# Arduino_4_Layer.net
KiCad netlist of a schematic drawn in Altium Designer
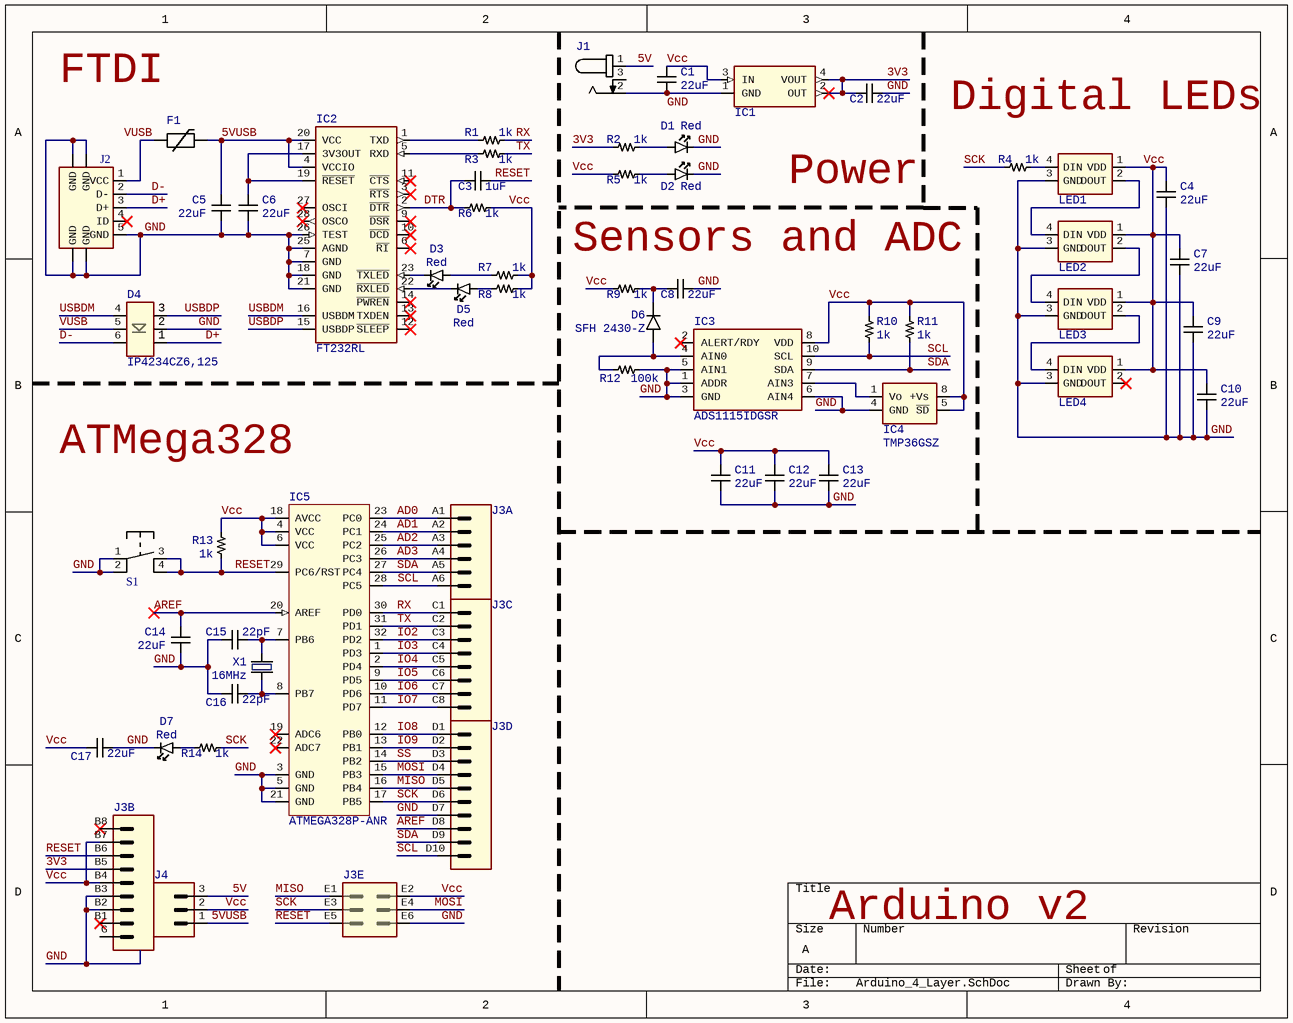
[diagram p0: Arduino_4_Layer.SchDoc]

(export (version "E")
  (design (tool "Eeschema 10.0.6"))
  (components
    (comp (ref "C1")
      (value "22uF")
      (footprint "CAP1206")
      (description "22µF ±20% 16V Ceramic Capacitor X5R 1206 (3216 Metric)")
      (fields (field (name "DIGIKEY PART") "1276-2728-1-ND"))
      (libsource (lib "Arduino_4_Layer") (part "1206_22uF"))
    )
    (comp (ref "C2")
      (value "22uF")
      (footprint "CAP1206")
      (description "22µF ±20% 16V Ceramic Capacitor X5R 1206 (3216 Metric)")
      (fields (field (name "DIGIKEY PART") "1276-2728-1-ND"))
      (libsource (lib "Arduino_4_Layer") (part "1206_22uF"))
    )
    (comp (ref "C3")
      (value "1uF")
      (footprint "CAP1206")
      (description "1µF ±20% 16V Ceramic Capacitor X7R 1206 (3216 Metric)")
      (fields (field (name "DIGIKEY PART") "399-8150-1-ND"))
      (libsource (lib "Arduino_4_Layer") (part "1206_1uF"))
    )
    (comp (ref "C4")
      (value "22uF")
      (footprint "CAP1206")
      (description "22µF ±20% 16V Ceramic Capacitor X5R 1206 (3216 Metric)")
      (fields (field (name "DIGIKEY PART") "1276-2728-1-ND"))
      (libsource (lib "Arduino_4_Layer") (part "1206_22uF"))
    )
    (comp (ref "C5")
      (value "22uF")
      (footprint "CAP1206")
      (description "22µF ±20% 16V Ceramic Capacitor X5R 1206 (3216 Metric)")
      (fields (field (name "DIGIKEY PART") "1276-2728-1-ND"))
      (libsource (lib "Arduino_4_Layer") (part "1206_22uF"))
    )
    (comp (ref "C6")
      (value "22uF")
      (footprint "CAP1206")
      (description "22µF ±20% 16V Ceramic Capacitor X5R 1206 (3216 Metric)")
      (fields (field (name "DIGIKEY PART") "1276-2728-1-ND"))
      (libsource (lib "Arduino_4_Layer") (part "1206_22uF"))
    )
    (comp (ref "C7")
      (value "22uF")
      (footprint "CAP1206")
      (description "22µF ±20% 16V Ceramic Capacitor X5R 1206 (3216 Metric)")
      (fields (field (name "DIGIKEY PART") "1276-2728-1-ND"))
      (libsource (lib "Arduino_4_Layer") (part "1206_22uF"))
    )
    (comp (ref "C8")
      (value "22uF")
      (footprint "CAP1206")
      (description "22µF ±20% 16V Ceramic Capacitor X5R 1206 (3216 Metric)")
      (fields (field (name "DIGIKEY PART") "1276-2728-1-ND"))
      (libsource (lib "Arduino_4_Layer") (part "1206_22uF"))
    )
    (comp (ref "C9")
      (value "22uF")
      (footprint "CAP1206")
      (description "22µF ±20% 16V Ceramic Capacitor X5R 1206 (3216 Metric)")
      (fields (field (name "DIGIKEY PART") "1276-2728-1-ND"))
      (libsource (lib "Arduino_4_Layer") (part "1206_22uF"))
    )
    (comp (ref "C10")
      (value "22uF")
      (footprint "CAP1206")
      (description "22µF ±20% 16V Ceramic Capacitor X5R 1206 (3216 Metric)")
      (fields (field (name "DIGIKEY PART") "1276-2728-1-ND"))
      (libsource (lib "Arduino_4_Layer") (part "1206_22uF"))
    )
    (comp (ref "C11")
      (value "22uF")
      (footprint "CAP1206")
      (description "22µF ±20% 16V Ceramic Capacitor X5R 1206 (3216 Metric)")
      (fields (field (name "DIGIKEY PART") "1276-2728-1-ND"))
      (libsource (lib "Arduino_4_Layer") (part "1206_22uF"))
    )
    (comp (ref "C12")
      (value "22uF")
      (footprint "CAP1206")
      (description "22µF ±20% 16V Ceramic Capacitor X5R 1206 (3216 Metric)")
      (fields (field (name "DIGIKEY PART") "1276-2728-1-ND"))
      (libsource (lib "Arduino_4_Layer") (part "1206_22uF"))
    )
    (comp (ref "C13")
      (value "22uF")
      (footprint "CAP1206")
      (description "22µF ±20% 16V Ceramic Capacitor X5R 1206 (3216 Metric)")
      (fields (field (name "DIGIKEY PART") "1276-2728-1-ND"))
      (libsource (lib "Arduino_4_Layer") (part "1206_22uF"))
    )
    (comp (ref "C14")
      (value "22uF")
      (footprint "CAP1206")
      (description "22µF ±20% 16V Ceramic Capacitor X5R 1206 (3216 Metric)")
      (fields (field (name "DIGIKEY PART") "1276-2728-1-ND"))
      (libsource (lib "Arduino_4_Layer") (part "1206_22uF"))
    )
    (comp (ref "C15")
      (value "22pF")
      (footprint "CAP1206")
      (description "22pF ±5% 16V Ceramic Capacitor C0G, NP0 1206 (3216 Metric)")
      (fields (field (name "DIGIKEY PART") "732-7867-1-ND"))
      (libsource (lib "Arduino_4_Layer") (part "1206_22pF"))
    )
    (comp (ref "C16")
      (value "22pF")
      (footprint "CAP1206")
      (description "22pF ±5% 16V Ceramic Capacitor C0G, NP0 1206 (3216 Metric)")
      (fields (field (name "DIGIKEY PART") "732-7867-1-ND"))
      (libsource (lib "Arduino_4_Layer") (part "1206_22pF"))
    )
    (comp (ref "C17")
      (value "22uF")
      (footprint "CAP1206")
      (description "22µF ±20% 16V Ceramic Capacitor X5R 1206 (3216 Metric)")
      (fields (field (name "DIGIKEY PART") "1276-2728-1-ND"))
      (libsource (lib "Arduino_4_Layer") (part "1206_22uF"))
    )
    (comp (ref "D1")
      (value "Red")
      (footprint "LED")
      (description "Red 638nm LED Indication - Discrete 1.8V 1206 (3216 Metric)")
      (fields (field (name "DIGIKEY PART") "160-1167-1-ND"))
      (libsource (lib "Arduino_4_Layer") (part "1206_RED_LED"))
    )
    (comp (ref "D2")
      (value "Red")
      (footprint "LED")
      (description "Red 638nm LED Indication - Discrete 1.8V 1206 (3216 Metric)")
      (fields (field (name "DIGIKEY PART") "160-1167-1-ND"))
      (libsource (lib "Arduino_4_Layer") (part "1206_RED_LED"))
    )
    (comp (ref "D3")
      (value "Red")
      (footprint "LED")
      (description "Red 638nm LED Indication - Discrete 1.8V 1206 (3216 Metric)")
      (fields (field (name "DIGIKEY PART") "160-1167-1-ND"))
      (libsource (lib "Arduino_4_Layer") (part "1206_RED_LED"))
    )
    (comp (ref "D4")
      (value "IP4234CZ6,125")
      (footprint "TSOP-6")
      (description "Clamp Ipp Tvs Diode Surface Mount 6-TSOP")
      (fields (field (name "DIGIKEY PART") "1727-4717-1-ND"))
      (libsource (lib "Arduino_4_Layer") (part "TVS_Diode"))
    )
    (comp (ref "D5")
      (value "Red")
      (footprint "LED")
      (description "Red 638nm LED Indication - Discrete 1.8V 1206 (3216 Metric)")
      (fields (field (name "DIGIKEY PART") "160-1167-1-ND"))
      (libsource (lib "Arduino_4_Layer") (part "1206_RED_LED"))
    )
    (comp (ref "D6")
      (value "SFH 2430-Z")
      (footprint "SFH 2430")
      (description "Ambient Light Sensor Photodiode Chip 570nm 0.17A/W Sensitivity Automotive 2-Pin DIL SMT")
      (fields (field (name "MANUFACTURER") "Osram Opto"))
      (libsource (lib "Arduino_4_Layer") (part "SFH 2430-Z"))
    )
    (comp (ref "D7")
      (value "Red")
      (footprint "LED")
      (description "Red 638nm LED Indication - Discrete 1.8V 1206 (3216 Metric)")
      (fields (field (name "DIGIKEY PART") "160-1167-1-ND"))
      (libsource (lib "Arduino_4_Layer") (part "1206_RED_LED"))
    )
    (comp (ref "F1")
      (value "MF-MSMF050-2")
      (footprint "FUSE")
      (description "Polymeric PTC Resettable Fuse 15V 500mA Ih Surface Mount 1812 (4532 Metric), Concave")
      (fields (field (name "DIGIKEY PART") "MF-MSMF050-2CT-ND"))
      (libsource (lib "Arduino_4_Layer") (part "Fuse"))
    )
    (comp (ref "IC1")
      (value "AZ1117CH-3.3TRG1")
      (footprint "SOT223")
      (description "Linear Voltage Regulator IC Positive Fixed 1 Output 1A SOT-223")
      (fields (field (name "DIGIKEY PART") "AZ1117CH-3.3TRG1DICT-ND"))
      (libsource (lib "Arduino_4_Layer") (part "3.3V_LDO"))
    )
    (comp (ref "IC2")
      (value "FT232RL")
      (footprint "SOP65P780X200-28N")
      (description "USB Bridge, USB to UART USB 2.0 UART Interface 28-SSOP")
      (fields (field (name "DIGIKEY PART") "768-1007-1-ND"))
      (libsource (lib "Arduino_4_Layer") (part "FTDI"))
    )
    (comp (ref "IC3")
      (value "ADS1115IDGSR")
      (footprint "VSSOP-10")
      (description "4-Channel Single ADC Delta-Sigma 860sps 16-bit Serial 10-Pin VSSOP T/R")
      (fields (field (name "MANUFACTURER") "Texas Instruments"))
      (libsource (lib "Arduino_4_Layer") (part "ADS1115IDGSR"))
    )
    (comp (ref "IC4")
      (value "TMP36GSZ")
      (footprint "SOIC-8")
      (description "Temp Sensor Analog(Voltage) Serial (2-Wire) 8-Pin SOIC N Tube")
      (fields (field (name "MANUFACTURER") "Analog Devices"))
      (libsource (lib "Arduino_4_Layer") (part "TMP36GSZ"))
    )
    (comp (ref "IC5")
      (value "ATMEGA328P-ANR")
      (footprint "TQFP-32")
      (description "AVR AVR® ATmega Microcontroller IC 8-Bit 20MHz 32KB (16K x 16) FLASH 32-TQFP (7x7)")
      (fields (field (name "DIGIKEY PART") "ATMEGA328P-ANRCT-ND"))
      (libsource (lib "Arduino_4_Layer") (part "ATMega328P"))
    )
    (comp (ref "J1")
      (value "Power Jack")
      (footprint "Power_Jack")
      (description "Power Barrel Connector Jack 2.10mm ID (0.083\"), 5.50mm OD (0.217\") Through Hole, Right Angle")
      (fields (field (name "DIGIKEY PART") "CP-102A-ND"))
      (libsource (lib "Arduino_4_Layer") (part "Power Jack"))
    )
    (comp (ref "J2")
      (value "XM7D-0512")
      (footprint "XM7D-0512")
      (description "USB - mini B USB 2.0 Receptacle Connector 5 Position Through Hole, Right Angle")
      (fields (field (name "DIGIKEY PART") "OR1205-ND"))
      (libsource (lib "Arduino_4_Layer") (part "USB"))
    )
    (comp (ref "J3")
      (value "Arduino_Shield")
      (footprint "ARDUINO_SHIELD")
      (libsource (lib "Arduino_4_Layer") (part "Arduino_Shield"))
    )
    (comp (ref "J4")
      (value "PREC003SAAN-RC")
      (footprint "3_PIN")
      (description "Connector Header Through Hole 3 position 0.100\" (2.54mm)")
      (fields (field (name "DIGIKEY PART") "S1012EC-03-ND"))
      (libsource (lib "Arduino_4_Layer") (part "3_PIN"))
    )
    (comp (ref "LED1")
      (value "IN-PI55QATPRPGPBPW-60")
      (footprint "PLCC_5x5")
      (description "Top View Plcc 5.0X5.0X1.6 4-PIN")
      (fields (field (name "MANUFACTURER") "Inolux"))
      (libsource (lib "Arduino_4_Layer") (part "IN-PI55QATPRPGPBPW-60"))
    )
    (comp (ref "LED2")
      (value "IN-PI55QATPRPGPBPW-60")
      (footprint "PLCC_5x5")
      (description "Top View Plcc 5.0X5.0X1.6 4-PIN")
      (fields (field (name "MANUFACTURER") "Inolux"))
      (libsource (lib "Arduino_4_Layer") (part "IN-PI55QATPRPGPBPW-60"))
    )
    (comp (ref "LED3")
      (value "IN-PI55QATPRPGPBPW-60")
      (footprint "PLCC_5x5")
      (description "Top View Plcc 5.0X5.0X1.6 4-PIN")
      (fields (field (name "MANUFACTURER") "Inolux"))
      (libsource (lib "Arduino_4_Layer") (part "IN-PI55QATPRPGPBPW-60"))
    )
    (comp (ref "LED4")
      (value "IN-PI55QATPRPGPBPW-60")
      (footprint "PLCC_5x5")
      (description "Top View Plcc 5.0X5.0X1.6 4-PIN")
      (fields (field (name "MANUFACTURER") "Inolux"))
      (libsource (lib "Arduino_4_Layer") (part "IN-PI55QATPRPGPBPW-60"))
    )
    (comp (ref "R1")
      (value "1k")
      (footprint "RES1206")
      (description "1 kOhms ±1% 0.5W, 1/2W Chip Resistor 1206 (3216 Metric) Anti-Sulfur, Moisture Resistant Thin Film")
      (fields (field (name "DIGIKEY PART") "RNCP1206FTD1K00CT-ND"))
      (libsource (lib "Arduino_4_Layer") (part "1206_1K"))
    )
    (comp (ref "R2")
      (value "1k")
      (footprint "RES1206")
      (description "1 kOhms ±1% 0.5W, 1/2W Chip Resistor 1206 (3216 Metric) Anti-Sulfur, Moisture Resistant Thin Film")
      (fields (field (name "DIGIKEY PART") "RNCP1206FTD1K00CT-ND"))
      (libsource (lib "Arduino_4_Layer") (part "1206_1K"))
    )
    (comp (ref "R3")
      (value "1k")
      (footprint "RES1206")
      (description "1 kOhms ±1% 0.5W, 1/2W Chip Resistor 1206 (3216 Metric) Anti-Sulfur, Moisture Resistant Thin Film")
      (fields (field (name "DIGIKEY PART") "RNCP1206FTD1K00CT-ND"))
      (libsource (lib "Arduino_4_Layer") (part "1206_1K"))
    )
    (comp (ref "R4")
      (value "1k")
      (footprint "RES1206")
      (description "1 kOhms ±1% 0.5W, 1/2W Chip Resistor 1206 (3216 Metric) Anti-Sulfur, Moisture Resistant Thin Film")
      (fields (field (name "DIGIKEY PART") "RNCP1206FTD1K00CT-ND"))
      (libsource (lib "Arduino_4_Layer") (part "1206_1K"))
    )
    (comp (ref "R5")
      (value "1k")
      (footprint "RES1206")
      (description "1 kOhms ±1% 0.5W, 1/2W Chip Resistor 1206 (3216 Metric) Anti-Sulfur, Moisture Resistant Thin Film")
      (fields (field (name "DIGIKEY PART") "RNCP1206FTD1K00CT-ND"))
      (libsource (lib "Arduino_4_Layer") (part "1206_1K"))
    )
    (comp (ref "R6")
      (value "1k")
      (footprint "RES1206")
      (description "1 kOhms ±1% 0.5W, 1/2W Chip Resistor 1206 (3216 Metric) Anti-Sulfur, Moisture Resistant Thin Film")
      (fields (field (name "DIGIKEY PART") "RNCP1206FTD1K00CT-ND"))
      (libsource (lib "Arduino_4_Layer") (part "1206_1K"))
    )
    (comp (ref "R7")
      (value "1k")
      (footprint "RES1206")
      (description "1 kOhms ±1% 0.5W, 1/2W Chip Resistor 1206 (3216 Metric) Anti-Sulfur, Moisture Resistant Thin Film")
      (fields (field (name "DIGIKEY PART") "RNCP1206FTD1K00CT-ND"))
      (libsource (lib "Arduino_4_Layer") (part "1206_1K"))
    )
    (comp (ref "R8")
      (value "1k")
      (footprint "RES1206")
      (description "1 kOhms ±1% 0.5W, 1/2W Chip Resistor 1206 (3216 Metric) Anti-Sulfur, Moisture Resistant Thin Film")
      (fields (field (name "DIGIKEY PART") "RNCP1206FTD1K00CT-ND"))
      (libsource (lib "Arduino_4_Layer") (part "1206_1K"))
    )
    (comp (ref "R9")
      (value "1k")
      (footprint "RES1206")
      (description "1 kOhms ±1% 0.5W, 1/2W Chip Resistor 1206 (3216 Metric) Anti-Sulfur, Moisture Resistant Thin Film")
      (fields (field (name "DIGIKEY PART") "RNCP1206FTD1K00CT-ND"))
      (libsource (lib "Arduino_4_Layer") (part "1206_1K"))
    )
    (comp (ref "R10")
      (value "1k")
      (footprint "RES1206")
      (description "1 kOhms ±1% 0.5W, 1/2W Chip Resistor 1206 (3216 Metric) Anti-Sulfur, Moisture Resistant Thin Film")
      (fields (field (name "DIGIKEY PART") "RNCP1206FTD1K00CT-ND"))
      (libsource (lib "Arduino_4_Layer") (part "1206_1K"))
    )
    (comp (ref "R11")
      (value "1k")
      (footprint "RES1206")
      (description "1 kOhms ±1% 0.5W, 1/2W Chip Resistor 1206 (3216 Metric) Anti-Sulfur, Moisture Resistant Thin Film")
      (fields (field (name "DIGIKEY PART") "RNCP1206FTD1K00CT-ND"))
      (libsource (lib "Arduino_4_Layer") (part "1206_1K"))
    )
    (comp (ref "R12")
      (value "100k")
      (footprint "RES1206")
      (description "100 kOhms ±5% 0.25W, 1/4W Chip Resistor 1206 (3216 Metric) Automotive AEC-Q200 Thick Film")
      (libsource (lib "Arduino_4_Layer") (part "1206_100k"))
    )
    (comp (ref "R13")
      (value "1k")
      (footprint "RES1206")
      (description "1 kOhms ±1% 0.5W, 1/2W Chip Resistor 1206 (3216 Metric) Anti-Sulfur, Moisture Resistant Thin Film")
      (fields (field (name "DIGIKEY PART") "RNCP1206FTD1K00CT-ND"))
      (libsource (lib "Arduino_4_Layer") (part "1206_1K"))
    )
    (comp (ref "R14")
      (value "1k")
      (footprint "RES1206")
      (description "1 kOhms ±1% 0.5W, 1/2W Chip Resistor 1206 (3216 Metric) Anti-Sulfur, Moisture Resistant Thin Film")
      (fields (field (name "DIGIKEY PART") "RNCP1206FTD1K00CT-ND"))
      (libsource (lib "Arduino_4_Layer") (part "1206_1K"))
    )
    (comp (ref "S1")
      (value "TL3305AF160QG")
      (footprint "Switch")
      (description "Tactile Switch SPST-NO Top Actuated Surface Mount")
      (fields (field (name "DIGIKEY PART") "EG5350CT-ND"))
      (libsource (lib "Arduino_4_Layer") (part "Push_Button"))
    )
    (comp (ref "X1")
      (value "16MHz")
      (footprint "Crystal")
      (description "16MHz ±30ppm Crystal 18pF 40 Ohms HC-49/US")
      (fields (field (name "DIGIKEY PART") "535-10226-1-ND"))
      (libsource (lib "Arduino_4_Layer") (part "16MHz_Crystal"))
    )
  )
  (nets
    (net (code "1") (name "/3V3") (class "Default")
      (node (ref "C2") (pin "2") (pinfunction "2_2") (pintype "passive"))
      (node (ref "IC1") (pin "2") (pinfunction "OUT_2") (pintype "output"))
      (node (ref "IC1") (pin "4") (pinfunction "VOUT_4") (pintype "output"))
      (node (ref "J3") (pin "B5") (pinfunction "5_B5") (pintype "passive"))
      (node (ref "R2") (pin "2") (pintype "passive"))
    )
    (net (code "2") (name "/5V") (class "Default")
      (node (ref "J1") (pin "1") (pinfunction "1_1") (pintype "passive"))
      (node (ref "J4") (pin "3") (pinfunction "3_3") (pintype "passive"))
    )
    (net (code "3") (name "/5VUSB") (class "Default")
      (node (ref "C5") (pin "2") (pinfunction "2_2") (pintype "passive"))
      (node (ref "F1") (pin "2") (pinfunction "2_2") (pintype "passive"))
      (node (ref "IC2") (pin "20") (pinfunction "VCC_20") (pintype "power_in"))
      (node (ref "IC2") (pin "4") (pinfunction "VCCIO_4") (pintype "power_in"))
      (node (ref "J4") (pin "1") (pinfunction "1_1") (pintype "passive"))
    )
    (net (code "4") (name "/AD0") (class "Default")
      (node (ref "IC5") (pin "23") (pinfunction "PC0_23") (pintype "bidirectional"))
      (node (ref "J3") (pin "A1") (pinfunction "1_A1") (pintype "passive"))
    )
    (net (code "5") (name "/AD1") (class "Default")
      (node (ref "IC5") (pin "24") (pinfunction "PC1_24") (pintype "bidirectional"))
      (node (ref "J3") (pin "A2") (pinfunction "2_A2") (pintype "passive"))
    )
    (net (code "6") (name "/AD2") (class "Default")
      (node (ref "IC5") (pin "25") (pinfunction "PC2_25") (pintype "bidirectional"))
      (node (ref "J3") (pin "A3") (pinfunction "3_A3") (pintype "passive"))
    )
    (net (code "7") (name "/AD3") (class "Default")
      (node (ref "IC5") (pin "26") (pinfunction "PC3_26") (pintype "bidirectional"))
      (node (ref "J3") (pin "A4") (pinfunction "4_A4") (pintype "passive"))
    )
    (net (code "8") (name "/AREF") (class "Default")
      (node (ref "C14") (pin "2") (pinfunction "2_2") (pintype "passive"))
      (node (ref "IC5") (pin "20") (pinfunction "AREF_20") (pintype "input"))
      (node (ref "J3") (pin "D8") (pinfunction "8_D8") (pintype "passive"))
    )
    (net (code "9") (name "/D+") (class "Default")
      (node (ref "D4") (pin "1") (pinfunction "1_1") (pintype "passive"))
      (node (ref "J2") (pin "3") (pinfunction "D+_3") (pintype "passive"))
    )
    (net (code "10") (name "/D-") (class "Default")
      (node (ref "D4") (pin "6") (pinfunction "6_6") (pintype "passive"))
      (node (ref "J2") (pin "2") (pinfunction "D-_2") (pintype "passive"))
    )
    (net (code "11") (name "/DTR") (class "Default")
      (node (ref "C3") (pin "1") (pinfunction "1_1") (pintype "passive"))
      (node (ref "IC2") (pin "2") (pinfunction "~{DTR}_2") (pintype "output"))
      (node (ref "R6") (pin "1") (pintype "passive"))
    )
    (net (code "12") (name "/GND") (class "Default")
      (node (ref "C1") (pin "2") (pinfunction "2_2") (pintype "passive"))
      (node (ref "C10") (pin "1") (pinfunction "1_1") (pintype "passive"))
      (node (ref "C11") (pin "1") (pinfunction "1_1") (pintype "passive"))
      (node (ref "C12") (pin "1") (pinfunction "1_1") (pintype "passive"))
      (node (ref "C13") (pin "1") (pinfunction "1_1") (pintype "passive"))
      (node (ref "C14") (pin "1") (pinfunction "1_1") (pintype "passive"))
      (node (ref "C15") (pin "1") (pinfunction "1_1") (pintype "passive"))
      (node (ref "C16") (pin "1") (pinfunction "1_1") (pintype "passive"))
      (node (ref "C17") (pin "1") (pinfunction "1_1") (pintype "passive"))
      (node (ref "C2") (pin "1") (pinfunction "1_1") (pintype "passive"))
      (node (ref "C4") (pin "1") (pinfunction "1_1") (pintype "passive"))
      (node (ref "C5") (pin "1") (pinfunction "1_1") (pintype "passive"))
      (node (ref "C6") (pin "1") (pinfunction "1_1") (pintype "passive"))
      (node (ref "C7") (pin "1") (pinfunction "1_1") (pintype "passive"))
      (node (ref "C8") (pin "2") (pinfunction "2_2") (pintype "passive"))
      (node (ref "C9") (pin "1") (pinfunction "1_1") (pintype "passive"))
      (node (ref "D1") (pin "1") (pinfunction "1_1") (pintype "passive"))
      (node (ref "D2") (pin "1") (pinfunction "1_1") (pintype "passive"))
      (node (ref "D4") (pin "2") (pinfunction "2_2") (pintype "passive"))
      (node (ref "D7") (pin "1") (pinfunction "1_1") (pintype "passive"))
      (node (ref "IC1") (pin "1") (pinfunction "GND_1") (pintype "passive"))
      (node (ref "IC2") (pin "18") (pinfunction "GND_18") (pintype "power_in"))
      (node (ref "IC2") (pin "21") (pinfunction "GND_21") (pintype "power_in"))
      (node (ref "IC2") (pin "25") (pinfunction "AGND_25") (pintype "power_in"))
      (node (ref "IC2") (pin "26") (pinfunction "TEST_26") (pintype "input"))
      (node (ref "IC2") (pin "7") (pinfunction "GND_7") (pintype "power_in"))
      (node (ref "IC3") (pin "1") (pinfunction "ADDR_1") (pintype "passive"))
      (node (ref "IC3") (pin "3") (pinfunction "GND_3") (pintype "passive"))
      (node (ref "IC3") (pin "5") (pinfunction "AIN1_5") (pintype "passive"))
      (node (ref "IC3") (pin "6") (pinfunction "AIN4_6") (pintype "passive"))
      (node (ref "IC4") (pin "4") (pinfunction "GND_4") (pintype "passive"))
      (node (ref "IC5") (pin "21") (pinfunction "GND_21") (pintype "power_in"))
      (node (ref "IC5") (pin "3") (pinfunction "GND_3") (pintype "power_in"))
      (node (ref "IC5") (pin "5") (pinfunction "GND_5") (pintype "power_in"))
      (node (ref "J1") (pin "2") (pinfunction "2_2") (pintype "passive"))
      (node (ref "J2") (pin "5") (pinfunction "GND_5") (pintype "passive"))
      (node (ref "J2") (pin "SH1") (pinfunction "GND_SH1") (pintype "passive"))
      (node (ref "J2") (pin "SH2") (pinfunction "GND_SH2") (pintype "passive"))
      (node (ref "J2") (pin "SH3") (pinfunction "GND_SH3") (pintype "passive"))
      (node (ref "J2") (pin "SH4") (pinfunction "GND_SH4") (pintype "passive"))
      (node (ref "J3") (pin "B2") (pinfunction "2_B2") (pintype "passive"))
      (node (ref "J3") (pin "B3") (pinfunction "3_B3") (pintype "passive"))
      (node (ref "J3") (pin "D7") (pinfunction "7_D7") (pintype "passive"))
      (node (ref "J3") (pin "E6") (pinfunction "6_E6") (pintype "passive"))
      (node (ref "LED1") (pin "3") (pinfunction "GND_3") (pintype "passive"))
      (node (ref "LED2") (pin "3") (pinfunction "GND_3") (pintype "passive"))
      (node (ref "LED3") (pin "3") (pinfunction "GND_3") (pintype "passive"))
      (node (ref "LED4") (pin "3") (pinfunction "GND_3") (pintype "passive"))
      (node (ref "R12") (pin "1") (pintype "passive"))
      (node (ref "S1") (pin "1") (pinfunction "1_1") (pintype "passive"))
      (node (ref "S1") (pin "2") (pinfunction "2_2") (pintype "passive"))
    )
    (net (code "13") (name "/IO2") (class "Default")
      (node (ref "IC5") (pin "32") (pinfunction "PD2_32") (pintype "bidirectional"))
      (node (ref "J3") (pin "C3") (pinfunction "3_C3") (pintype "passive"))
    )
    (net (code "14") (name "/IO3") (class "Default")
      (node (ref "IC5") (pin "1") (pinfunction "PD3_1") (pintype "bidirectional"))
      (node (ref "J3") (pin "C4") (pinfunction "4_C4") (pintype "passive"))
    )
    (net (code "15") (name "/IO4") (class "Default")
      (node (ref "IC5") (pin "2") (pinfunction "PD4_2") (pintype "bidirectional"))
      (node (ref "J3") (pin "C5") (pinfunction "5_C5") (pintype "passive"))
    )
    (net (code "16") (name "/IO5") (class "Default")
      (node (ref "IC5") (pin "9") (pinfunction "PD5_9") (pintype "bidirectional"))
      (node (ref "J3") (pin "C6") (pinfunction "6_C6") (pintype "passive"))
    )
    (net (code "17") (name "/IO6") (class "Default")
      (node (ref "IC5") (pin "10") (pinfunction "PD6_10") (pintype "bidirectional"))
      (node (ref "J3") (pin "C7") (pinfunction "7_C7") (pintype "passive"))
    )
    (net (code "18") (name "/IO7") (class "Default")
      (node (ref "IC5") (pin "11") (pinfunction "PD7_11") (pintype "bidirectional"))
      (node (ref "J3") (pin "C8") (pinfunction "8_C8") (pintype "passive"))
    )
    (net (code "19") (name "/IO8") (class "Default")
      (node (ref "IC5") (pin "12") (pinfunction "PB0_12") (pintype "bidirectional"))
      (node (ref "J3") (pin "D1") (pinfunction "1_D1") (pintype "passive"))
    )
    (net (code "20") (name "/IO9") (class "Default")
      (node (ref "IC5") (pin "13") (pinfunction "PB1_13") (pintype "bidirectional"))
      (node (ref "J3") (pin "D2") (pinfunction "2_D2") (pintype "passive"))
    )
    (net (code "21") (name "/MISO") (class "Default")
      (node (ref "IC5") (pin "16") (pinfunction "PB4_16") (pintype "bidirectional"))
      (node (ref "J3") (pin "D5") (pinfunction "5_D5") (pintype "passive"))
      (node (ref "J3") (pin "E1") (pinfunction "1_E1") (pintype "passive"))
    )
    (net (code "22") (name "/MOSI") (class "Default")
      (node (ref "IC5") (pin "15") (pinfunction "PB3_15") (pintype "bidirectional"))
      (node (ref "J3") (pin "D4") (pinfunction "4_D4") (pintype "passive"))
      (node (ref "J3") (pin "E4") (pinfunction "5_E4") (pintype "passive"))
    )
    (net (code "23") (name "/RESET") (class "Default")
      (node (ref "C3") (pin "2") (pinfunction "2_2") (pintype "passive"))
      (node (ref "IC5") (pin "29") (pinfunction "PC6/RST_29") (pintype "bidirectional"))
      (node (ref "J3") (pin "B6") (pinfunction "6_B6") (pintype "passive"))
      (node (ref "J3") (pin "E5") (pinfunction "3_E5") (pintype "passive"))
      (node (ref "R13") (pin "1") (pintype "passive"))
      (node (ref "S1") (pin "3") (pinfunction "3_3") (pintype "passive"))
      (node (ref "S1") (pin "4") (pinfunction "4_4") (pintype "passive"))
    )
    (net (code "24") (name "/RX") (class "Default")
      (node (ref "IC5") (pin "30") (pinfunction "PD0_30") (pintype "bidirectional"))
      (node (ref "J3") (pin "C1") (pinfunction "1_C1") (pintype "passive"))
      (node (ref "R1") (pin "2") (pintype "passive"))
    )
    (net (code "25") (name "/SCK") (class "Default")
      (node (ref "IC5") (pin "17") (pinfunction "PB5_17") (pintype "bidirectional"))
      (node (ref "J3") (pin "D6") (pinfunction "6_D6") (pintype "passive"))
      (node (ref "J3") (pin "E3") (pinfunction "2_E3") (pintype "passive"))
      (node (ref "R14") (pin "2") (pintype "passive"))
      (node (ref "R4") (pin "1") (pintype "passive"))
    )
    (net (code "26") (name "/SCL") (class "Default")
      (node (ref "IC3") (pin "10") (pinfunction "SCL_10") (pintype "passive"))
      (node (ref "IC5") (pin "28") (pinfunction "PC5_28") (pintype "bidirectional"))
      (node (ref "J3") (pin "A6") (pinfunction "6_A6") (pintype "passive"))
      (node (ref "J3") (pin "D10") (pinfunction "10_D10") (pintype "passive"))
      (node (ref "R10") (pin "1") (pintype "passive"))
    )
    (net (code "27") (name "/SDA") (class "Default")
      (node (ref "IC3") (pin "9") (pinfunction "SDA_9") (pintype "passive"))
      (node (ref "IC5") (pin "27") (pinfunction "PC4_27") (pintype "bidirectional"))
      (node (ref "J3") (pin "A5") (pinfunction "5_A5") (pintype "passive"))
      (node (ref "J3") (pin "D9") (pinfunction "9_D9") (pintype "passive"))
      (node (ref "R11") (pin "1") (pintype "passive"))
    )
    (net (code "28") (name "/SS") (class "Default")
      (node (ref "IC5") (pin "14") (pinfunction "PB2_14") (pintype "bidirectional"))
      (node (ref "J3") (pin "D3") (pinfunction "3_D3") (pintype "passive"))
    )
    (net (code "29") (name "/TX") (class "Default")
      (node (ref "IC5") (pin "31") (pinfunction "PD1_31") (pintype "bidirectional"))
      (node (ref "J3") (pin "C2") (pinfunction "2_C2") (pintype "passive"))
      (node (ref "R3") (pin "2") (pintype "passive"))
    )
    (net (code "30") (name "/USBDM") (class "Default")
      (node (ref "D4") (pin "4") (pinfunction "4_4") (pintype "passive"))
      (node (ref "IC2") (pin "16") (pinfunction "USBDM_16") (pintype "bidirectional"))
    )
    (net (code "31") (name "/USBDP") (class "Default")
      (node (ref "D4") (pin "3") (pinfunction "3_3") (pintype "passive"))
      (node (ref "IC2") (pin "15") (pinfunction "USBDP_15") (pintype "bidirectional"))
    )
    (net (code "32") (name "/VUSB") (class "Default")
      (node (ref "D4") (pin "5") (pinfunction "5_5") (pintype "passive"))
      (node (ref "F1") (pin "1") (pinfunction "1_1") (pintype "passive"))
      (node (ref "J2") (pin "1") (pinfunction "VCC_1") (pintype "passive"))
    )
    (net (code "33") (name "/Vcc") (class "Default")
      (node (ref "C1") (pin "1") (pinfunction "1_1") (pintype "passive"))
      (node (ref "C10") (pin "2") (pinfunction "2_2") (pintype "passive"))
      (node (ref "C11") (pin "2") (pinfunction "2_2") (pintype "passive"))
      (node (ref "C12") (pin "2") (pinfunction "2_2") (pintype "passive"))
      (node (ref "C13") (pin "2") (pinfunction "2_2") (pintype "passive"))
      (node (ref "C17") (pin "2") (pinfunction "2_2") (pintype "passive"))
      (node (ref "C4") (pin "2") (pinfunction "2_2") (pintype "passive"))
      (node (ref "C7") (pin "2") (pinfunction "2_2") (pintype "passive"))
      (node (ref "C9") (pin "2") (pinfunction "2_2") (pintype "passive"))
      (node (ref "IC1") (pin "3") (pinfunction "IN_3") (pintype "input"))
      (node (ref "IC3") (pin "8") (pinfunction "VDD_8") (pintype "passive"))
      (node (ref "IC4") (pin "5") (pinfunction "~{SD}_5") (pintype "passive"))
      (node (ref "IC4") (pin "8") (pinfunction "+Vs_8") (pintype "passive"))
      (node (ref "IC5") (pin "18") (pinfunction "AVCC_18") (pintype "power_in"))
      (node (ref "IC5") (pin "4") (pinfunction "VCC_4") (pintype "power_in"))
      (node (ref "IC5") (pin "6") (pinfunction "VCC_6") (pintype "power_in"))
      (node (ref "J3") (pin "B4") (pinfunction "4_B4") (pintype "passive"))
      (node (ref "J3") (pin "B7") (pinfunction "7_B7") (pintype "passive"))
      (node (ref "J3") (pin "E2") (pinfunction "4_E2") (pintype "passive"))
      (node (ref "J4") (pin "2") (pinfunction "2_2") (pintype "passive"))
      (node (ref "LED1") (pin "1") (pinfunction "VDD_1") (pintype "passive"))
      (node (ref "LED2") (pin "1") (pinfunction "VDD_1") (pintype "passive"))
      (node (ref "LED3") (pin "1") (pinfunction "VDD_1") (pintype "passive"))
      (node (ref "LED4") (pin "1") (pinfunction "VDD_1") (pintype "passive"))
      (node (ref "R10") (pin "2") (pintype "passive"))
      (node (ref "R11") (pin "2") (pintype "passive"))
      (node (ref "R13") (pin "2") (pintype "passive"))
      (node (ref "R5") (pin "2") (pintype "passive"))
      (node (ref "R6") (pin "2") (pintype "passive"))
      (node (ref "R7") (pin "2") (pintype "passive"))
      (node (ref "R8") (pin "2") (pintype "passive"))
      (node (ref "R9") (pin "2") (pintype "passive"))
    )
    (net (code "34") (name "Net-(C8-Pad1)") (class "Default")
      (node (ref "C8") (pin "1") (pinfunction "1_1") (pintype "passive"))
      (node (ref "D6") (pin "C") (pinfunction "C_C") (pintype "passive"))
      (node (ref "R9") (pin "1") (pintype "passive"))
    )
    (net (code "35") (name "Net-(D1-Pad2)") (class "Default")
      (node (ref "D1") (pin "2") (pinfunction "2_2") (pintype "passive"))
      (node (ref "R2") (pin "1") (pintype "passive"))
    )
    (net (code "36") (name "Net-(D2-Pad2)") (class "Default")
      (node (ref "D2") (pin "2") (pinfunction "2_2") (pintype "passive"))
      (node (ref "R5") (pin "1") (pintype "passive"))
    )
    (net (code "37") (name "Net-(D3-Pad2)") (class "Default")
      (node (ref "D3") (pin "2") (pinfunction "2_2") (pintype "passive"))
      (node (ref "R7") (pin "1") (pintype "passive"))
    )
    (net (code "38") (name "Net-(D5-Pad2)") (class "Default")
      (node (ref "D5") (pin "2") (pinfunction "2_2") (pintype "passive"))
      (node (ref "R8") (pin "1") (pintype "passive"))
    )
    (net (code "39") (name "Net-(D7-Pad2)") (class "Default")
      (node (ref "D7") (pin "2") (pinfunction "2_2") (pintype "passive"))
      (node (ref "R14") (pin "1") (pintype "passive"))
    )
    (net (code "40") (name "Net-(IC2-3V3OUT)") (class "Default")
      (node (ref "C6") (pin "2") (pinfunction "2_2") (pintype "passive"))
      (node (ref "IC2") (pin "17") (pinfunction "3V3OUT_17") (pintype "power_in"))
      (node (ref "IC2") (pin "19") (pinfunction "~{RESET}_19") (pintype "passive"))
    )
    (net (code "41") (name "Net-(IC2-RXD)") (class "Default")
      (node (ref "IC2") (pin "5") (pinfunction "RXD_5") (pintype "input"))
      (node (ref "R3") (pin "1") (pintype "passive"))
    )
    (net (code "42") (name "Net-(IC2-TXD)") (class "Default")
      (node (ref "IC2") (pin "1") (pinfunction "TXD_1") (pintype "output"))
      (node (ref "R1") (pin "1") (pintype "passive"))
    )
    (net (code "43") (name "Net-(IC2-~{RXLED})") (class "Default")
      (node (ref "D5") (pin "1") (pinfunction "1_1") (pintype "passive"))
      (node (ref "IC2") (pin "22") (pinfunction "~{RXLED}_22") (pintype "input"))
    )
    (net (code "44") (name "Net-(IC2-~{TXLED})") (class "Default")
      (node (ref "D3") (pin "1") (pinfunction "1_1") (pintype "passive"))
      (node (ref "IC2") (pin "23") (pinfunction "~{TXLED}_23") (pintype "input"))
    )
    (net (code "45") (name "Net-(IC3-AIN0)") (class "Default")
      (node (ref "D6") (pin "A") (pinfunction "A_A") (pintype "passive"))
      (node (ref "IC3") (pin "4") (pinfunction "AIN0_4") (pintype "passive"))
      (node (ref "R12") (pin "2") (pintype "passive"))
    )
    (net (code "46") (name "Net-(IC3-AIN3)") (class "Default")
      (node (ref "IC3") (pin "7") (pinfunction "AIN3_7") (pintype "passive"))
      (node (ref "IC4") (pin "1") (pinfunction "Vo_1") (pintype "passive"))
    )
    (net (code "47") (name "Net-(IC5-PB6)") (class "Default")
      (node (ref "C15") (pin "2") (pinfunction "2_2") (pintype "passive"))
      (node (ref "IC5") (pin "7") (pinfunction "PB6_7") (pintype "bidirectional"))
      (node (ref "X1") (pin "2") (pinfunction "2_2") (pintype "passive"))
    )
    (net (code "48") (name "Net-(IC5-PB7)") (class "Default")
      (node (ref "C16") (pin "2") (pinfunction "2_2") (pintype "passive"))
      (node (ref "IC5") (pin "8") (pinfunction "PB7_8") (pintype "bidirectional"))
      (node (ref "X1") (pin "1") (pinfunction "1_1") (pintype "passive"))
    )
    (net (code "49") (name "Net-(LED1-DIN)") (class "Default")
      (node (ref "LED1") (pin "4") (pinfunction "DIN_4") (pintype "passive"))
      (node (ref "R4") (pin "2") (pintype "passive"))
    )
    (net (code "50") (name "Net-(LED1-DOUT)") (class "Default")
      (node (ref "LED1") (pin "2") (pinfunction "DOUT_2") (pintype "passive"))
      (node (ref "LED2") (pin "4") (pinfunction "DIN_4") (pintype "passive"))
    )
    (net (code "51") (name "Net-(LED2-DOUT)") (class "Default")
      (node (ref "LED2") (pin "2") (pinfunction "DOUT_2") (pintype "passive"))
      (node (ref "LED3") (pin "4") (pinfunction "DIN_4") (pintype "passive"))
    )
    (net (code "52") (name "Net-(LED3-DOUT)") (class "Default")
      (node (ref "LED3") (pin "2") (pinfunction "DOUT_2") (pintype "passive"))
      (node (ref "LED4") (pin "4") (pinfunction "DIN_4") (pintype "passive"))
    )
    (net (code "53") (name "unconnected-(IC2-OSCI-Pad27)") (class "Default")
      (node (ref "IC2") (pin "27") (pinfunction "OSCI_27") (pintype "passive+no_connect"))
    )
    (net (code "54") (name "unconnected-(IC2-OSCO-Pad28)") (class "Default")
      (node (ref "IC2") (pin "28") (pinfunction "OSCO_28") (pintype "output+no_connect"))
    )
    (net (code "55") (name "unconnected-(IC2-TXDEN-Pad13)") (class "Default")
      (node (ref "IC2") (pin "13") (pinfunction "TXDEN_13") (pintype "passive+no_connect"))
    )
    (net (code "56") (name "unconnected-(IC2-~{CTS}-Pad11)") (class "Default")
      (node (ref "IC2") (pin "11") (pinfunction "~{CTS}_11") (pintype "input+no_connect"))
    )
    (net (code "57") (name "unconnected-(IC2-~{DCD}-Pad10)") (class "Default")
      (node (ref "IC2") (pin "10") (pinfunction "~{DCD}_10") (pintype "passive+no_connect"))
    )
    (net (code "58") (name "unconnected-(IC2-~{DSR}-Pad9)") (class "Default")
      (node (ref "IC2") (pin "9") (pinfunction "~{DSR}_9") (pintype "passive+no_connect"))
    )
    (net (code "59") (name "unconnected-(IC2-~{PWREN}-Pad14)") (class "Default")
      (node (ref "IC2") (pin "14") (pinfunction "~{PWREN}_14") (pintype "passive+no_connect"))
    )
    (net (code "60") (name "unconnected-(IC2-~{RI}-Pad6)") (class "Default")
      (node (ref "IC2") (pin "6") (pinfunction "~{RI}_6") (pintype "passive+no_connect"))
    )
    (net (code "61") (name "unconnected-(IC2-~{RTS}-Pad3)") (class "Default")
      (node (ref "IC2") (pin "3") (pinfunction "~{RTS}_3") (pintype "output+no_connect"))
    )
    (net (code "62") (name "unconnected-(IC2-~{SLEEP}-Pad12)") (class "Default")
      (node (ref "IC2") (pin "12") (pinfunction "~{SLEEP}_12") (pintype "passive+no_connect"))
    )
    (net (code "63") (name "unconnected-(IC3-ALERT{slash}RDY-Pad2)") (class "Default")
      (node (ref "IC3") (pin "2") (pinfunction "ALERT/RDY_2") (pintype "passive+no_connect"))
    )
    (net (code "64") (name "unconnected-(IC5-ADC6-Pad19)") (class "Default")
      (node (ref "IC5") (pin "19") (pinfunction "ADC6_19") (pintype "bidirectional+no_connect"))
    )
    (net (code "65") (name "unconnected-(IC5-ADC7-Pad22)") (class "Default")
      (node (ref "IC5") (pin "22") (pinfunction "ADC7_22") (pintype "bidirectional+no_connect"))
    )
    (net (code "66") (name "unconnected-(J1-Pad3)") (class "Default")
      (node (ref "J1") (pin "3") (pinfunction "3_3") (pintype "passive"))
    )
    (net (code "67") (name "unconnected-(J2-ID-Pad4)") (class "Default")
      (node (ref "J2") (pin "4") (pinfunction "ID_4") (pintype "passive+no_connect"))
    )
    (net (code "68") (name "unconnected-(J3B-1-PadB1)") (class "Default")
      (node (ref "J3") (pin "B1") (pinfunction "1_B1") (pintype "passive+no_connect"))
    )
    (net (code "69") (name "unconnected-(J3B-8-PadB8)") (class "Default")
      (node (ref "J3") (pin "B8") (pinfunction "8_B8") (pintype "passive+no_connect"))
    )
    (net (code "70") (name "unconnected-(J3B-GND-PadG)") (class "Default")
      (node (ref "J3") (pin "G") (pinfunction "GND_G") (pintype "passive"))
    )
    (net (code "71") (name "unconnected-(LED4-DOUT-Pad2)") (class "Default")
      (node (ref "LED4") (pin "2") (pinfunction "DOUT_2") (pintype "passive+no_connect"))
    )
  )
)
